# mimic1705.net
KiCad netlist of a schematic drawn in EAGLE
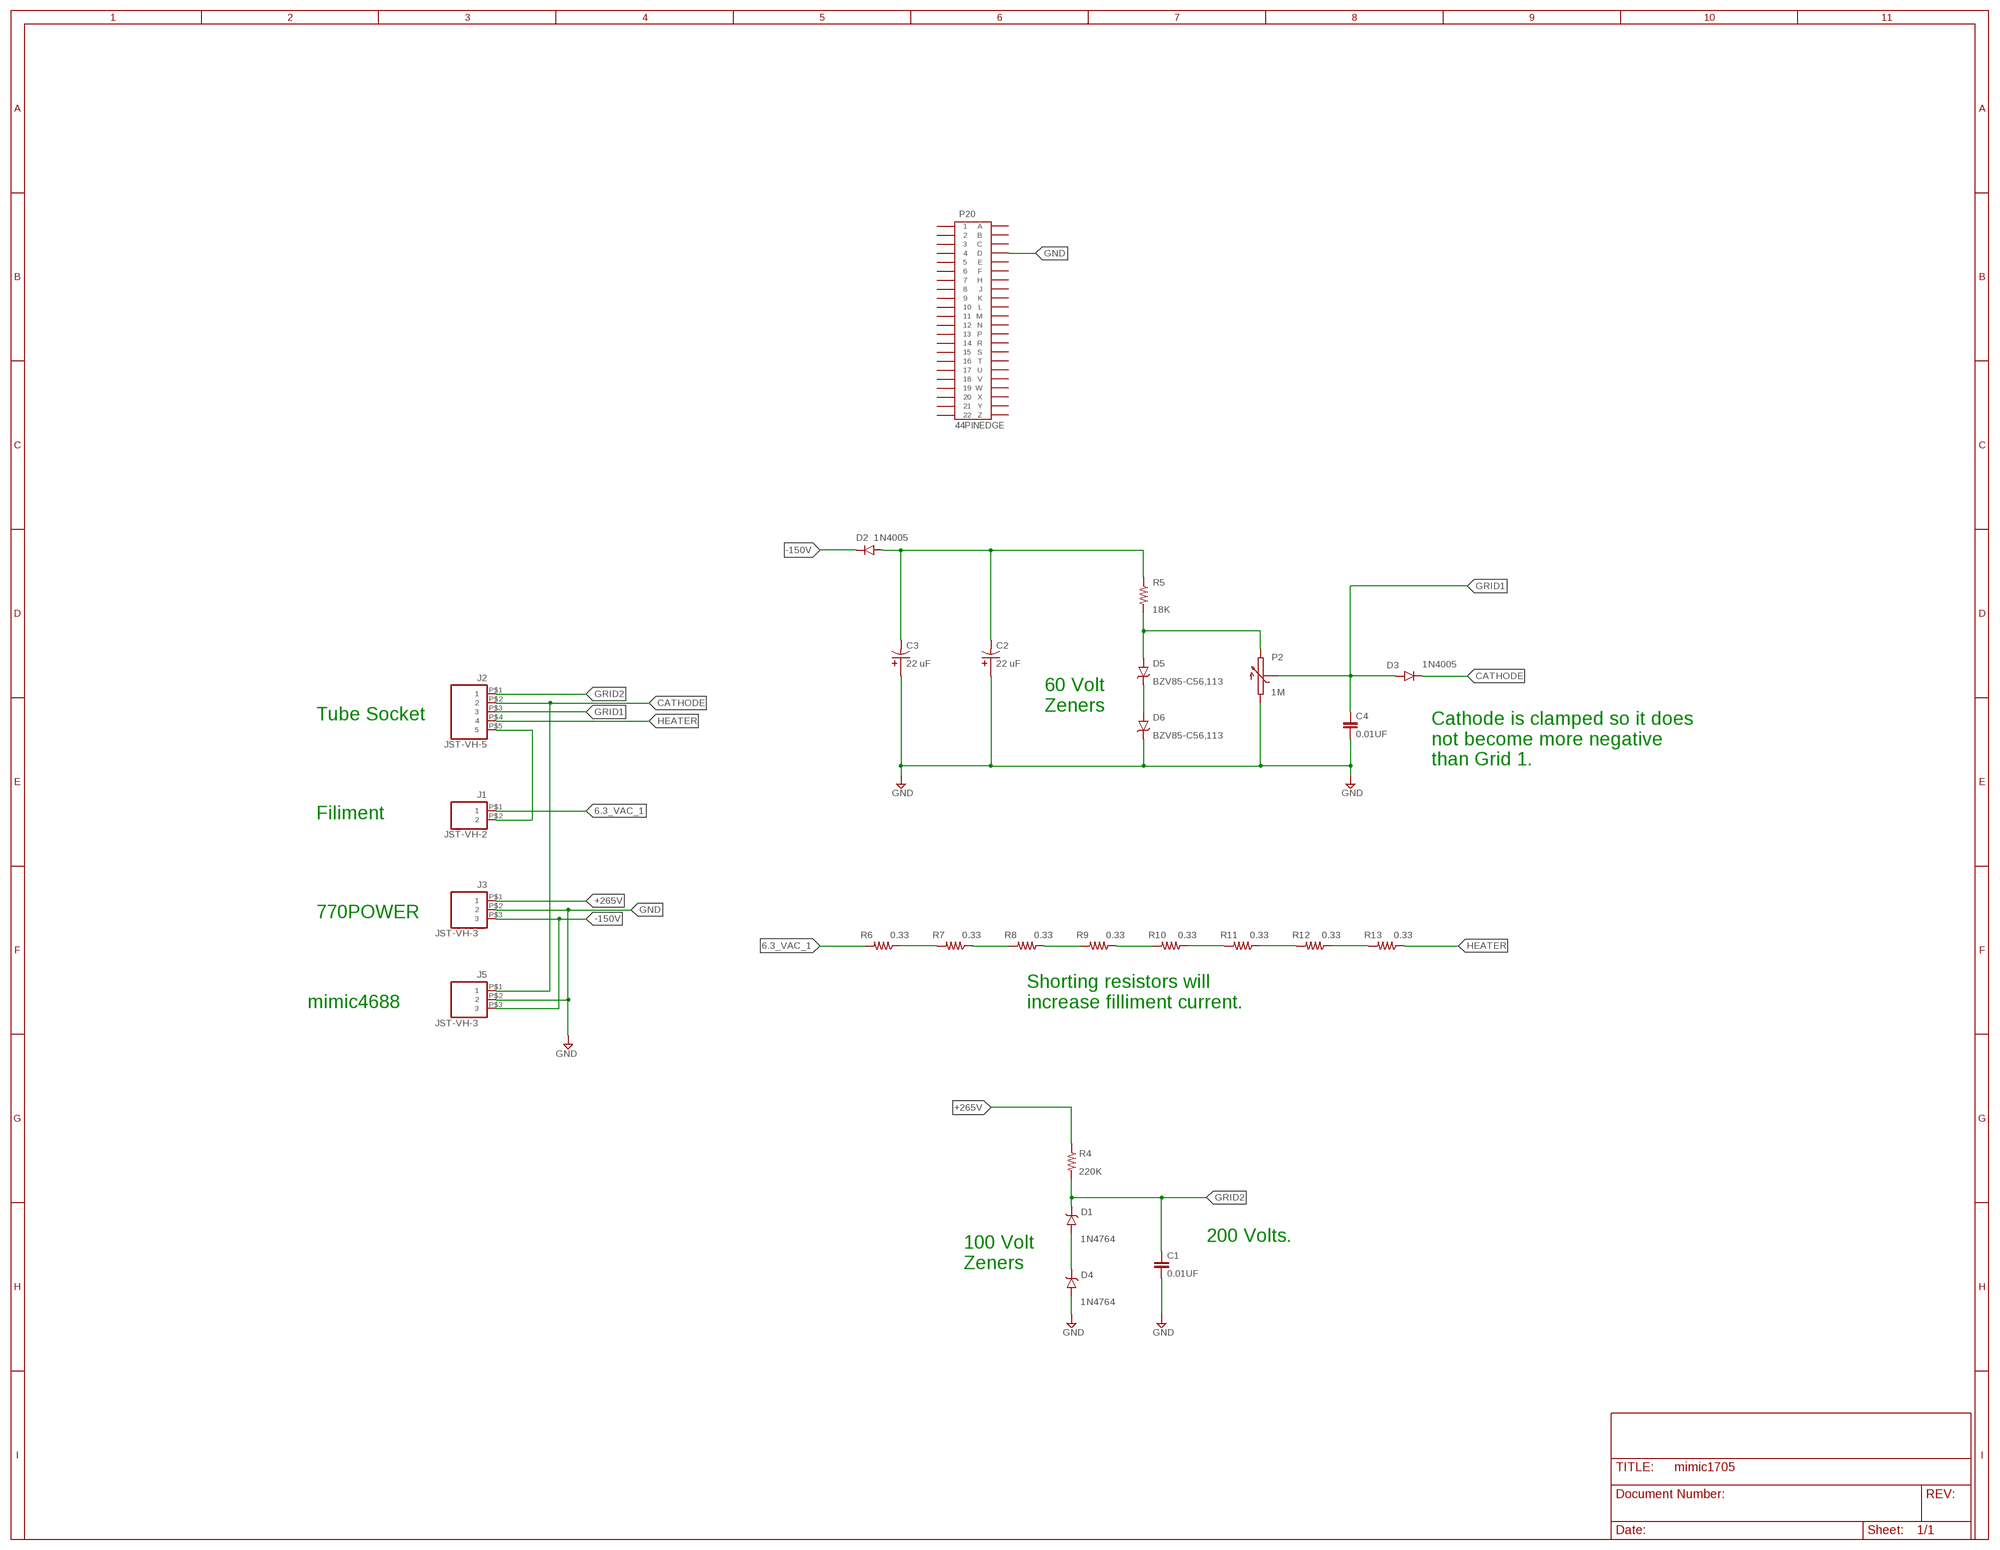
[diagram p0: schematic, sheet 1]

(export (version "E")
  (design (tool "Eeschema 10.0.6"))
  (components
    (comp (ref "C1")
      (value "0.01UF")
      (footprint "eagle-import:5MM_TH")
      (libsource (lib "eagle-import") (part "CAP_5MM"))
    )
    (comp (ref "C2")
      (value "22 uF")
      (footprint "eagle-import:AXIAL10X26")
      (libsource (lib "eagle-import") (part "CAP100UF200V"))
    )
    (comp (ref "C3")
      (value "22 uF")
      (footprint "eagle-import:AXIAL10X26")
      (libsource (lib "eagle-import") (part "CAP100UF200V"))
    )
    (comp (ref "C4")
      (value "0.01UF")
      (footprint "eagle-import:5MM_TH")
      (libsource (lib "eagle-import") (part "CAP_5MM"))
    )
    (comp (ref "D1")
      (value "1N4764")
      (footprint "eagle-import:DO-41-10")
      (libsource (lib "eagle-import") (part "1N4764A"))
    )
    (comp (ref "D2")
      (value "1N4005")
      (footprint "eagle-import:DO-41-10")
      (libsource (lib "eagle-import") (part "1N400X"))
    )
    (comp (ref "D3")
      (value "1N4005")
      (footprint "eagle-import:DO-41-10")
      (libsource (lib "eagle-import") (part "1N400X"))
    )
    (comp (ref "D4")
      (value "1N4764")
      (footprint "eagle-import:DO-41-10")
      (libsource (lib "eagle-import") (part "1N4764A"))
    )
    (comp (ref "D5")
      (value "BZV85-C56,113")
      (footprint "eagle-import:DO-41-10")
      (libsource (lib "eagle-import") (part "BZV85-C56,113"))
    )
    (comp (ref "D6")
      (value "BZV85-C56,113")
      (footprint "eagle-import:DO-41-10")
      (libsource (lib "eagle-import") (part "BZV85-C56,113"))
    )
    (comp (ref "J1")
      (value "JST-VH-2")
      (footprint "eagle-import:VHR-2N")
      (libsource (lib "eagle-import") (part "JST-VH-2"))
    )
    (comp (ref "J2")
      (value "JST-VH-5")
      (footprint "eagle-import:VHR-5N")
      (libsource (lib "eagle-import") (part "JST-VH-5"))
    )
    (comp (ref "J3")
      (value "JST-VH-3")
      (footprint "eagle-import:VHR-3N")
      (libsource (lib "eagle-import") (part "JST-VH-3"))
    )
    (comp (ref "J5")
      (value "JST-VH-3")
      (footprint "eagle-import:VHR-3N")
      (libsource (lib "eagle-import") (part "JST-VH-3"))
    )
    (comp (ref "P2")
      (value "1M")
      (footprint "eagle-import:3006P")
      (libsource (lib "eagle-import") (part "POT-3006P"))
    )
    (comp (ref "P20")
      (value "44PINEDGE")
      (footprint "eagle-import:44PINEDGE")
      (libsource (lib "eagle-import") (part "44PINEDGE"))
    )
    (comp (ref "R4")
      (value "220K")
      (footprint "eagle-import:0207_10")
      (libsource (lib "eagle-import") (part "RES-V"))
    )
    (comp (ref "R5")
      (value "18K")
      (footprint "eagle-import:0207_10")
      (libsource (lib "eagle-import") (part "RES-V"))
    )
    (comp (ref "R6")
      (value "0.33")
      (footprint "eagle-import:0309_12")
      (libsource (lib "eagle-import") (part "R-1/2WATT"))
    )
    (comp (ref "R7")
      (value "0.33")
      (footprint "eagle-import:0309_12")
      (libsource (lib "eagle-import") (part "R-1/2WATT"))
    )
    (comp (ref "R8")
      (value "0.33")
      (footprint "eagle-import:0309_12")
      (libsource (lib "eagle-import") (part "R-1/2WATT"))
    )
    (comp (ref "R9")
      (value "0.33")
      (footprint "eagle-import:0309_12")
      (libsource (lib "eagle-import") (part "R-1/2WATT"))
    )
    (comp (ref "R10")
      (value "0.33")
      (footprint "eagle-import:0309_12")
      (libsource (lib "eagle-import") (part "R-1/2WATT"))
    )
    (comp (ref "R11")
      (value "0.33")
      (footprint "eagle-import:0309_12")
      (libsource (lib "eagle-import") (part "R-1/2WATT"))
    )
    (comp (ref "R12")
      (value "0.33")
      (footprint "eagle-import:0309_12")
      (libsource (lib "eagle-import") (part "R-1/2WATT"))
    )
    (comp (ref "R13")
      (value "0.33")
      (footprint "eagle-import:0309_12")
      (libsource (lib "eagle-import") (part "R-1/2WATT"))
    )
  )
  (nets
    (net (code "1") (name "+265V") (class "Default")
      (node (ref "J3") (pin "P$1") (pinfunction "1_P$1") (pintype "bidirectional"))
      (node (ref "R4") (pin "1") (pinfunction "P$1_1") (pintype "passive"))
    )
    (net (code "2") (name "-150V") (class "Default")
      (node (ref "D2") (pin "C") (pinfunction "C_C") (pintype "passive"))
      (node (ref "J3") (pin "P$3") (pinfunction "3_P$3") (pintype "bidirectional"))
      (node (ref "J5") (pin "P$3") (pinfunction "3_P$3") (pintype "bidirectional"))
    )
    (net (code "3") (name "6.3_VAC_1") (class "Default")
      (node (ref "J1") (pin "P$1") (pinfunction "1_P$1") (pintype "bidirectional"))
      (node (ref "R6") (pin "2") (pinfunction "P$2_2") (pintype "passive"))
    )
    (net (code "4") (name "CATHODE") (class "Default")
      (node (ref "D3") (pin "C") (pinfunction "C_C") (pintype "passive"))
      (node (ref "J2") (pin "P$2") (pinfunction "2_P$2") (pintype "bidirectional"))
      (node (ref "J5") (pin "P$1") (pinfunction "1_P$1") (pintype "bidirectional"))
    )
    (net (code "5") (name "GND") (class "Default")
      (node (ref "C1") (pin "2") (pinfunction "2_2") (pintype "passive"))
      (node (ref "C2") (pin "P$1") (pinfunction "1_P$1") (pintype "passive"))
      (node (ref "C3") (pin "P$1") (pinfunction "1_P$1") (pintype "passive"))
      (node (ref "C4") (pin "2") (pinfunction "2_2") (pintype "passive"))
      (node (ref "D4") (pin "A") (pinfunction "A_A") (pintype "passive"))
      (node (ref "D6") (pin "C") (pinfunction "C_C") (pintype "passive"))
      (node (ref "J3") (pin "P$2") (pinfunction "2_P$2") (pintype "bidirectional"))
      (node (ref "J5") (pin "P$2") (pinfunction "2_P$2") (pintype "bidirectional"))
      (node (ref "P2") (pin "1") (pinfunction "1_1") (pintype "passive"))
      (node (ref "P20") (pin "D") (pinfunction "D_D") (pintype "passive"))
    )
    (net (code "6") (name "GRID1") (class "Default")
      (node (ref "C4") (pin "1") (pinfunction "1_1") (pintype "passive"))
      (node (ref "D3") (pin "A") (pinfunction "A_A") (pintype "passive"))
      (node (ref "J2") (pin "P$3") (pinfunction "3_P$3") (pintype "bidirectional"))
      (node (ref "P2") (pin "2") (pinfunction "2_2") (pintype "passive"))
    )
    (net (code "7") (name "GRID2") (class "Default")
      (node (ref "C1") (pin "1") (pinfunction "1_1") (pintype "passive"))
      (node (ref "D1") (pin "C") (pinfunction "C_C") (pintype "passive"))
      (node (ref "J2") (pin "P$1") (pinfunction "1_P$1") (pintype "bidirectional"))
      (node (ref "R4") (pin "2") (pinfunction "P$2_2") (pintype "passive"))
    )
    (net (code "8") (name "HEATER") (class "Default")
      (node (ref "J2") (pin "P$4") (pinfunction "4_P$4") (pintype "bidirectional"))
      (node (ref "R13") (pin "1") (pinfunction "P$1_1") (pintype "passive"))
    )
    (net (code "9") (name "Net-(C2-2)") (class "Default")
      (node (ref "C2") (pin "P$2") (pinfunction "2_P$2") (pintype "passive"))
      (node (ref "C3") (pin "P$2") (pinfunction "2_P$2") (pintype "passive"))
      (node (ref "D2") (pin "A") (pinfunction "A_A") (pintype "passive"))
      (node (ref "R5") (pin "1") (pinfunction "P$1_1") (pintype "passive"))
    )
    (net (code "10") (name "Net-(D1-PadA)") (class "Default")
      (node (ref "D1") (pin "A") (pinfunction "A_A") (pintype "passive"))
      (node (ref "D4") (pin "C") (pinfunction "C_C") (pintype "passive"))
    )
    (net (code "11") (name "Net-(D5-PadC)") (class "Default")
      (node (ref "D5") (pin "C") (pinfunction "C_C") (pintype "passive"))
      (node (ref "D6") (pin "A") (pinfunction "A_A") (pintype "passive"))
    )
    (net (code "12") (name "Net-(J1-2)") (class "Default")
      (node (ref "J1") (pin "P$2") (pinfunction "2_P$2") (pintype "bidirectional"))
      (node (ref "J2") (pin "P$5") (pinfunction "5_P$5") (pintype "bidirectional"))
    )
    (net (code "13") (name "Net-(R5-P$2)") (class "Default")
      (node (ref "D5") (pin "A") (pinfunction "A_A") (pintype "passive"))
      (node (ref "P2") (pin "3") (pinfunction "3_3") (pintype "passive"))
      (node (ref "R5") (pin "2") (pinfunction "P$2_2") (pintype "passive"))
    )
    (net (code "14") (name "Net-(R6-P$1)") (class "Default")
      (node (ref "R6") (pin "1") (pinfunction "P$1_1") (pintype "passive"))
      (node (ref "R7") (pin "2") (pinfunction "P$2_2") (pintype "passive"))
    )
    (net (code "15") (name "Net-(R7-P$1)") (class "Default")
      (node (ref "R7") (pin "1") (pinfunction "P$1_1") (pintype "passive"))
      (node (ref "R8") (pin "2") (pinfunction "P$2_2") (pintype "passive"))
    )
    (net (code "16") (name "Net-(R8-P$1)") (class "Default")
      (node (ref "R8") (pin "1") (pinfunction "P$1_1") (pintype "passive"))
      (node (ref "R9") (pin "2") (pinfunction "P$2_2") (pintype "passive"))
    )
    (net (code "17") (name "Net-(R10-P$1)") (class "Default")
      (node (ref "R10") (pin "1") (pinfunction "P$1_1") (pintype "passive"))
      (node (ref "R11") (pin "2") (pinfunction "P$2_2") (pintype "passive"))
    )
    (net (code "18") (name "Net-(R10-P$2)") (class "Default")
      (node (ref "R10") (pin "2") (pinfunction "P$2_2") (pintype "passive"))
      (node (ref "R9") (pin "1") (pinfunction "P$1_1") (pintype "passive"))
    )
    (net (code "19") (name "Net-(R11-P$1)") (class "Default")
      (node (ref "R11") (pin "1") (pinfunction "P$1_1") (pintype "passive"))
      (node (ref "R12") (pin "2") (pinfunction "P$2_2") (pintype "passive"))
    )
    (net (code "20") (name "Net-(R12-P$1)") (class "Default")
      (node (ref "R12") (pin "1") (pinfunction "P$1_1") (pintype "passive"))
      (node (ref "R13") (pin "2") (pinfunction "P$2_2") (pintype "passive"))
    )
    (net (code "21") (name "unconnected-(P20-Pad1)") (class "Default")
      (node (ref "P20") (pin "1") (pinfunction "1_1") (pintype "passive"))
    )
    (net (code "22") (name "unconnected-(P20-Pad2)") (class "Default")
      (node (ref "P20") (pin "2") (pinfunction "2_2") (pintype "passive"))
    )
    (net (code "23") (name "unconnected-(P20-Pad3)") (class "Default")
      (node (ref "P20") (pin "3") (pinfunction "3_3") (pintype "passive"))
    )
    (net (code "24") (name "unconnected-(P20-Pad4)") (class "Default")
      (node (ref "P20") (pin "4") (pinfunction "4_4") (pintype "passive"))
    )
    (net (code "25") (name "unconnected-(P20-Pad5)") (class "Default")
      (node (ref "P20") (pin "5") (pinfunction "5_5") (pintype "passive"))
    )
    (net (code "26") (name "unconnected-(P20-Pad6)") (class "Default")
      (node (ref "P20") (pin "6") (pinfunction "6_6") (pintype "passive"))
    )
    (net (code "27") (name "unconnected-(P20-Pad7)") (class "Default")
      (node (ref "P20") (pin "7") (pinfunction "7_7") (pintype "passive"))
    )
    (net (code "28") (name "unconnected-(P20-Pad8)") (class "Default")
      (node (ref "P20") (pin "8") (pinfunction "8_8") (pintype "passive"))
    )
    (net (code "29") (name "unconnected-(P20-Pad9)") (class "Default")
      (node (ref "P20") (pin "9") (pinfunction "9_9") (pintype "passive"))
    )
    (net (code "30") (name "unconnected-(P20-Pad10)") (class "Default")
      (node (ref "P20") (pin "10") (pinfunction "10_10") (pintype "passive"))
    )
    (net (code "31") (name "unconnected-(P20-Pad11)") (class "Default")
      (node (ref "P20") (pin "11") (pinfunction "11_11") (pintype "passive"))
    )
    (net (code "32") (name "unconnected-(P20-Pad12)") (class "Default")
      (node (ref "P20") (pin "12") (pinfunction "12_12") (pintype "passive"))
    )
    (net (code "33") (name "unconnected-(P20-Pad13)") (class "Default")
      (node (ref "P20") (pin "13") (pinfunction "13_13") (pintype "passive"))
    )
    (net (code "34") (name "unconnected-(P20-Pad14)") (class "Default")
      (node (ref "P20") (pin "14") (pinfunction "14_14") (pintype "passive"))
    )
    (net (code "35") (name "unconnected-(P20-Pad15)") (class "Default")
      (node (ref "P20") (pin "15") (pinfunction "15_15") (pintype "passive"))
    )
    (net (code "36") (name "unconnected-(P20-Pad16)") (class "Default")
      (node (ref "P20") (pin "16") (pinfunction "16_16") (pintype "passive"))
    )
    (net (code "37") (name "unconnected-(P20-Pad17)") (class "Default")
      (node (ref "P20") (pin "17") (pinfunction "17_17") (pintype "passive"))
    )
    (net (code "38") (name "unconnected-(P20-Pad18)") (class "Default")
      (node (ref "P20") (pin "18") (pinfunction "18_18") (pintype "passive"))
    )
    (net (code "39") (name "unconnected-(P20-Pad19)") (class "Default")
      (node (ref "P20") (pin "19") (pinfunction "19_19") (pintype "passive"))
    )
    (net (code "40") (name "unconnected-(P20-Pad20)") (class "Default")
      (node (ref "P20") (pin "20") (pinfunction "20_20") (pintype "passive"))
    )
    (net (code "41") (name "unconnected-(P20-Pad21)") (class "Default")
      (node (ref "P20") (pin "21") (pinfunction "21_21") (pintype "passive"))
    )
    (net (code "42") (name "unconnected-(P20-Pad22)") (class "Default")
      (node (ref "P20") (pin "22") (pinfunction "22_22") (pintype "passive"))
    )
    (net (code "43") (name "unconnected-(P20-PadA)") (class "Default")
      (node (ref "P20") (pin "A") (pinfunction "A_A") (pintype "passive"))
    )
    (net (code "44") (name "unconnected-(P20-PadB)") (class "Default")
      (node (ref "P20") (pin "B") (pinfunction "B_B") (pintype "passive"))
    )
    (net (code "45") (name "unconnected-(P20-PadC)") (class "Default")
      (node (ref "P20") (pin "C") (pinfunction "C_C") (pintype "passive"))
    )
    (net (code "46") (name "unconnected-(P20-PadE)") (class "Default")
      (node (ref "P20") (pin "E") (pinfunction "E_E") (pintype "passive"))
    )
    (net (code "47") (name "unconnected-(P20-PadF)") (class "Default")
      (node (ref "P20") (pin "F") (pinfunction "F_F") (pintype "passive"))
    )
    (net (code "48") (name "unconnected-(P20-PadH)") (class "Default")
      (node (ref "P20") (pin "H") (pinfunction "H_H") (pintype "passive"))
    )
    (net (code "49") (name "unconnected-(P20-PadJ)") (class "Default")
      (node (ref "P20") (pin "J") (pinfunction "J_J") (pintype "passive"))
    )
    (net (code "50") (name "unconnected-(P20-PadK)") (class "Default")
      (node (ref "P20") (pin "K") (pinfunction "K_K") (pintype "passive"))
    )
    (net (code "51") (name "unconnected-(P20-PadL)") (class "Default")
      (node (ref "P20") (pin "L") (pinfunction "L_L") (pintype "passive"))
    )
    (net (code "52") (name "unconnected-(P20-PadM)") (class "Default")
      (node (ref "P20") (pin "M") (pinfunction "M_M") (pintype "passive"))
    )
    (net (code "53") (name "unconnected-(P20-PadN)") (class "Default")
      (node (ref "P20") (pin "N") (pinfunction "N_N") (pintype "passive"))
    )
    (net (code "54") (name "unconnected-(P20-PadP)") (class "Default")
      (node (ref "P20") (pin "P") (pinfunction "P_P") (pintype "passive"))
    )
    (net (code "55") (name "unconnected-(P20-PadR)") (class "Default")
      (node (ref "P20") (pin "R") (pinfunction "R_R") (pintype "passive"))
    )
    (net (code "56") (name "unconnected-(P20-PadS)") (class "Default")
      (node (ref "P20") (pin "S") (pinfunction "S_S") (pintype "passive"))
    )
    (net (code "57") (name "unconnected-(P20-PadT)") (class "Default")
      (node (ref "P20") (pin "T") (pinfunction "T_T") (pintype "passive"))
    )
    (net (code "58") (name "unconnected-(P20-PadU)") (class "Default")
      (node (ref "P20") (pin "U") (pinfunction "U_U") (pintype "passive"))
    )
    (net (code "59") (name "unconnected-(P20-PadV)") (class "Default")
      (node (ref "P20") (pin "V") (pinfunction "V_V") (pintype "passive"))
    )
    (net (code "60") (name "unconnected-(P20-PadW)") (class "Default")
      (node (ref "P20") (pin "W") (pinfunction "W_W") (pintype "passive"))
    )
    (net (code "61") (name "unconnected-(P20-PadX)") (class "Default")
      (node (ref "P20") (pin "X") (pinfunction "X_X") (pintype "passive"))
    )
    (net (code "62") (name "unconnected-(P20-PadY)") (class "Default")
      (node (ref "P20") (pin "Y") (pinfunction "Y_Y") (pintype "passive"))
    )
    (net (code "63") (name "unconnected-(P20-PadZ)") (class "Default")
      (node (ref "P20") (pin "Z") (pinfunction "Z_Z") (pintype "passive"))
    )
  )
)
